# power-supplies.net
KiCad netlist of a schematic drawn in Altium Designer
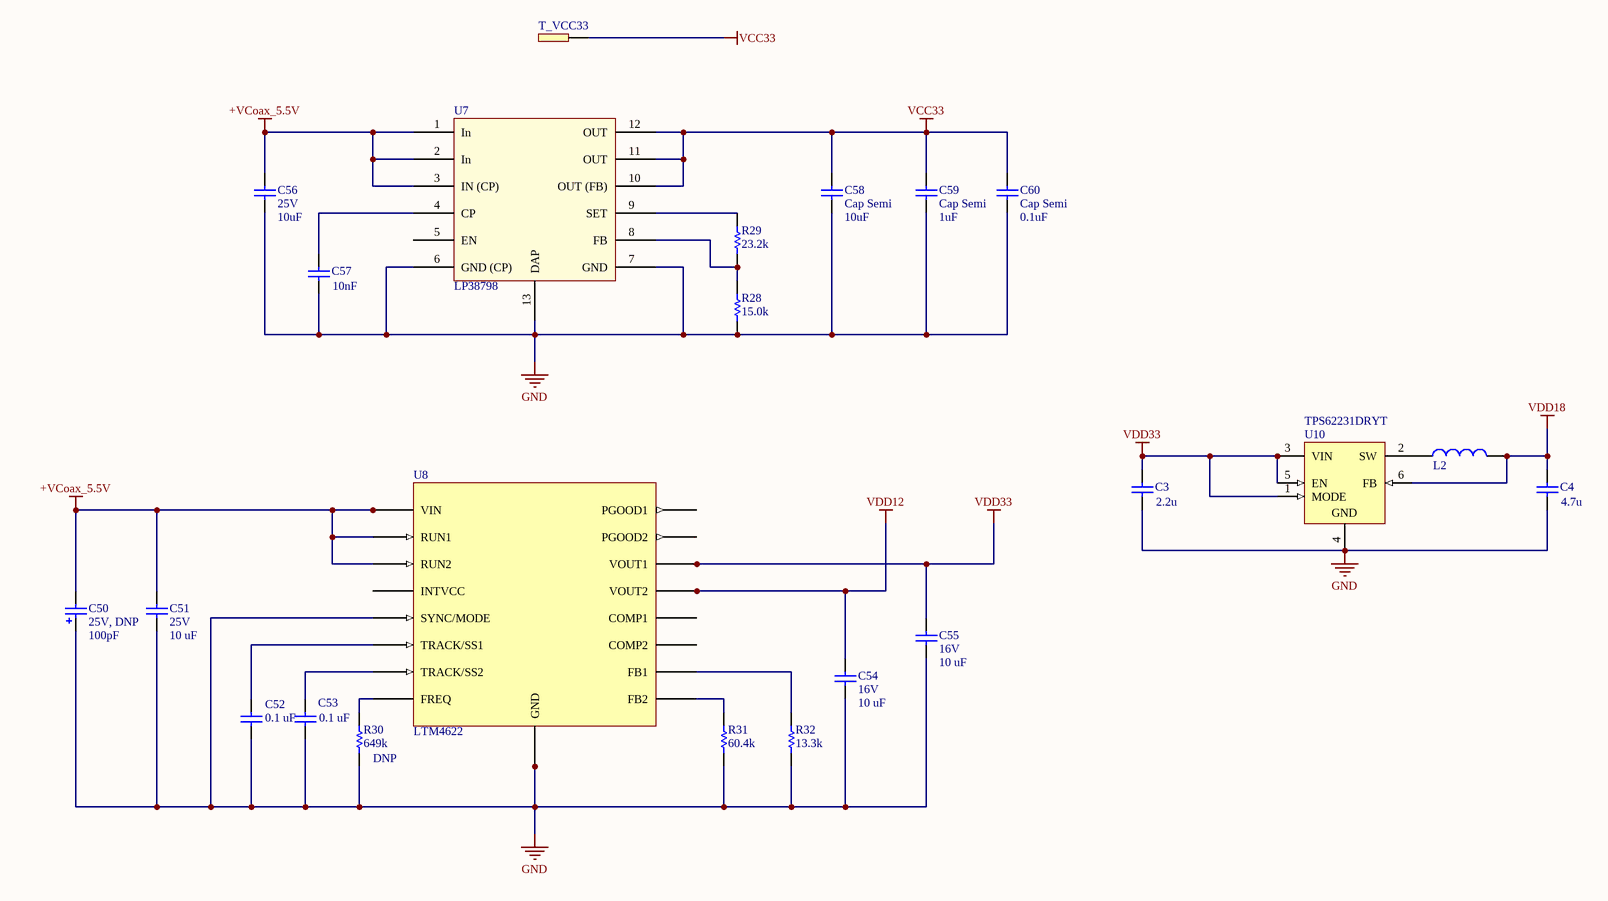
[diagram p0: power-supplies.SchDoc]

(export (version "E")
  (design (tool "Eeschema 10.0.6"))
  (components
    (comp (ref "C3")
      (value "2.2u")
      (footprint "Cap_0402")
      (description "Capacitor")
      (fields (field (name "Comment") "X7R Ceramic") (field (name "PUBLISHER") "Altium Limited"))
      (libsource (lib "Miscellaneous Devices") (part "Cap"))
    )
    (comp (ref "C4")
      (value "4.7u")
      (footprint "Cap_0402")
      (description "Capacitor")
      (fields (field (name "Comment") "X7R Ceramic") (field (name "PUBLISHER") "Altium Limited"))
      (libsource (lib "Miscellaneous Devices") (part "Cap"))
    )
    (comp (ref "C50")
      (value "25V, DNP")
      (footprint "C0805")
      (description "Polarized Capacitor (Surface Mount)")
      (fields (field (name "ALTIUM_VALUE") "100pF") (field (name "PUBLISHER") "Altium Limited"))
      (libsource (lib "Miscellaneous Devices") (part "Cap Pol3"))
    )
    (comp (ref "C51")
      (value "25V")
      (footprint "C1206")
      (description "Capacitor (Semiconductor SIM Model)")
      (fields
        (field (name "ALTIUM_VALUE") "10 uF")
        (field (name "VOLTAGE") "25 V")
        (field (name "PUBLISHER") "Altium Limited")
      )
      (libsource (lib "Miscellaneous Devices") (part "Cap Semi"))
    )
    (comp (ref "C52")
      (value "0.1 uF")
      (footprint "C1206")
      (description "Capacitor (Semiconductor SIM Model)")
      (fields
        (field (name "VOLTAGE") "25 V")
        (field (name "Comment") "25V")
        (field (name "PUBLISHER") "Altium Limited")
      )
      (libsource (lib "Miscellaneous Devices") (part "Cap Semi"))
    )
    (comp (ref "C53")
      (value "0.1 uF")
      (footprint "C1206")
      (description "Capacitor (Semiconductor SIM Model)")
      (fields
        (field (name "VOLTAGE") "25 V")
        (field (name "Comment") "25V")
        (field (name "PUBLISHER") "Altium Limited")
      )
      (libsource (lib "Miscellaneous Devices") (part "Cap Semi"))
    )
    (comp (ref "C54")
      (value "16V")
      (footprint "C1206")
      (description "Capacitor (Semiconductor SIM Model)")
      (fields
        (field (name "ALTIUM_VALUE") "10 uF")
        (field (name "VOLTAGE") "16 V")
        (field (name "PUBLISHER") "Altium Limited")
      )
      (libsource (lib "Miscellaneous Devices") (part "Cap Semi"))
    )
    (comp (ref "C55")
      (value "16V")
      (footprint "C1206")
      (description "Capacitor (Semiconductor SIM Model)")
      (fields
        (field (name "ALTIUM_VALUE") "10 uF")
        (field (name "VOLTAGE") "16 V")
        (field (name "PUBLISHER") "Altium Limited")
      )
      (libsource (lib "Miscellaneous Devices") (part "Cap Semi"))
    )
    (comp (ref "C56")
      (value "25V")
      (footprint "C1206")
      (description "Capacitor (Semiconductor SIM Model)")
      (fields (field (name "ALTIUM_VALUE") "10uF") (field (name "PUBLISHER") "Altium Limited"))
      (libsource (lib "Miscellaneous Devices") (part "Cap Semi"))
    )
    (comp (ref "C57")
      (value "10nF")
      (footprint "0402")
      (description "Capacitor (Semiconductor SIM Model)")
      (fields (field (name "PUBLISHER") "Altium Limited"))
      (libsource (lib "Miscellaneous Devices") (part "Cap Semi"))
    )
    (comp (ref "C58")
      (value "Cap Semi")
      (footprint "Cap-0603")
      (description "Capacitor (Semiconductor SIM Model)")
      (fields (field (name "ALTIUM_VALUE") "10uF") (field (name "PUBLISHER") "Altium Limited"))
      (libsource (lib "Miscellaneous Devices") (part "Cap Semi"))
    )
    (comp (ref "C59")
      (value "Cap Semi")
      (footprint "Cap-0603")
      (description "Capacitor (Semiconductor SIM Model)")
      (fields (field (name "ALTIUM_VALUE") "1uF") (field (name "PUBLISHER") "Altium Limited"))
      (libsource (lib "Miscellaneous Devices") (part "Cap Semi"))
    )
    (comp (ref "C60")
      (value "Cap Semi")
      (footprint "Cap-0603")
      (description "Capacitor (Semiconductor SIM Model)")
      (fields (field (name "ALTIUM_VALUE") "0.1uF") (field (name "PUBLISHER") "Altium Limited"))
      (libsource (lib "Miscellaneous Devices") (part "Cap Semi"))
    )
    (comp (ref "L2")
      (value "Ferrite Bead")
      (footprint "LQM21PN2R2MC0D")
      (libsource (lib "DA_Component_Library") (part "Ferrite Bead"))
    )
    (comp (ref "R28")
      (value "15.0k")
      (footprint "Res_0402")
      (description "Resistor")
      (fields (field (name "Comment") "Res1") (field (name "PUBLISHER") "Altium Limited"))
      (libsource (lib "Miscellaneous Devices") (part "Res1"))
    )
    (comp (ref "R29")
      (value "23.2k")
      (footprint "Res_0402")
      (description "Resistor")
      (fields (field (name "Comment") "Res1") (field (name "PUBLISHER") "Altium Limited"))
      (libsource (lib "Miscellaneous Devices") (part "Res1"))
    )
    (comp (ref "R30")
      (value "DNP")
      (footprint "Res_0402")
      (description "Resistor")
      (fields (field (name "ALTIUM_VALUE") "649k") (field (name "PUBLISHER") "Altium Limited"))
      (libsource (lib "Miscellaneous Devices") (part "Res1"))
    )
    (comp (ref "R31")
      (value "60.4k")
      (footprint "Res_0402")
      (description "Resistor")
      (fields (field (name "Comment") "649k (DNP)") (field (name "PUBLISHER") "Altium Limited"))
      (libsource (lib "Miscellaneous Devices") (part "Res1"))
    )
    (comp (ref "R32")
      (value "13.3k")
      (footprint "Res_0402")
      (description "Resistor")
      (fields (field (name "PUBLISHER") "Altium Limited"))
      (libsource (lib "Miscellaneous Devices") (part "Res1"))
    )
    (comp (ref "T_VCC33")
      (value "Header_1PIN")
      (footprint "JUMPER1PIN")
      (libsource (lib "Jack_SCH_Lib1") (part "Header_1PIN"))
    )
    (comp (ref "U7")
      (value "LP38798")
      (footprint "DFN12")
      (description "Low Noise Positive LDO")
      (libsource (lib "jonnew") (part "Component_1"))
    )
    (comp (ref "U8") (value "LTM4622") (footprint "LGA5x5") (libsource (lib "jonnew") (part "LTM4622")))
    (comp (ref "U10")
      (value "TPS62231DRYT")
      (footprint "TPS62231DRYT")
      (fields (field (name "MANUFACTURER") "Texas Instruments"))
      (libsource (lib "TI Power Management Step-Down Regulator") (part "TPS62231DRYT"))
    )
  )
  (nets
    (net (code "1") (name "+VCoax_5.5V") (class "Default")
      (node (ref "C50") (pin "2") (pinfunction "2_2") (pintype "passive"))
      (node (ref "C51") (pin "2") (pinfunction "2_2") (pintype "passive"))
      (node (ref "C56") (pin "2") (pinfunction "2_2") (pintype "passive"))
      (node (ref "U7") (pin "1") (pinfunction "In_1") (pintype "power_in"))
      (node (ref "U7") (pin "2") (pinfunction "In_2") (pintype "power_in"))
      (node (ref "U7") (pin "3") (pinfunction "IN_(CP)_3") (pintype "power_in"))
      (node (ref "U8") (pin "A2") (pinfunction "VIN_A2") (pintype "power_in"))
      (node (ref "U8") (pin "B2") (pinfunction "RUN2_B2") (pintype "input"))
      (node (ref "U8") (pin "B3") (pinfunction "VIN_B3") (pintype "passive"))
      (node (ref "U8") (pin "D2") (pinfunction "RUN1_D2") (pintype "input"))
      (node (ref "U8") (pin "D3") (pinfunction "VIN_D3") (pintype "passive"))
      (node (ref "U8") (pin "E2") (pinfunction "VIN_E2") (pintype "passive"))
    )
    (net (code "2") (name "GND") (class "Default")
      (node (ref "C3") (pin "1") (pinfunction "1_1") (pintype "passive"))
      (node (ref "C4") (pin "1") (pinfunction "1_1") (pintype "passive"))
      (node (ref "C50") (pin "1") (pinfunction "1_1") (pintype "passive"))
      (node (ref "C51") (pin "1") (pinfunction "1_1") (pintype "passive"))
      (node (ref "C52") (pin "1") (pinfunction "1_1") (pintype "passive"))
      (node (ref "C53") (pin "1") (pinfunction "1_1") (pintype "passive"))
      (node (ref "C54") (pin "1") (pinfunction "1_1") (pintype "passive"))
      (node (ref "C55") (pin "1") (pinfunction "1_1") (pintype "passive"))
      (node (ref "C56") (pin "1") (pinfunction "1_1") (pintype "passive"))
      (node (ref "C57") (pin "1") (pinfunction "1_1") (pintype "passive"))
      (node (ref "C58") (pin "1") (pinfunction "1_1") (pintype "passive"))
      (node (ref "C59") (pin "1") (pinfunction "1_1") (pintype "passive"))
      (node (ref "C60") (pin "1") (pinfunction "1_1") (pintype "passive"))
      (node (ref "R28") (pin "2") (pinfunction "2_2") (pintype "passive"))
      (node (ref "R30") (pin "2") (pinfunction "2_2") (pintype "passive"))
      (node (ref "R31") (pin "2") (pinfunction "2_2") (pintype "passive"))
      (node (ref "R32") (pin "2") (pinfunction "2_2") (pintype "passive"))
      (node (ref "U10") (pin "4") (pinfunction "GND_4") (pintype "power_in"))
      (node (ref "U7") (pin "13") (pinfunction "DAP_13") (pintype "passive"))
      (node (ref "U7") (pin "6") (pinfunction "GND_(CP)_6") (pintype "passive"))
      (node (ref "U7") (pin "7") (pinfunction "GND_7") (pintype "power_in"))
      (node (ref "U8") (pin "B5") (pinfunction "GND_B5") (pintype "passive"))
      (node (ref "U8") (pin "C1") (pinfunction "GND_C1") (pintype "power_in"))
      (node (ref "U8") (pin "C2") (pinfunction "GND_C2") (pintype "passive"))
      (node (ref "U8") (pin "C5") (pinfunction "SYNC/MODE_C5") (pintype "input"))
      (node (ref "U8") (pin "D5") (pinfunction "GND_D5") (pintype "passive"))
    )
    (net (code "3") (name "Net-(U7-CP)") (class "Default")
      (node (ref "C57") (pin "2") (pinfunction "2_2") (pintype "passive"))
      (node (ref "U7") (pin "4") (pinfunction "CP_4") (pintype "passive"))
    )
    (net (code "4") (name "Net-(U7-FB)") (class "Default")
      (node (ref "R28") (pin "1") (pinfunction "1_1") (pintype "passive"))
      (node (ref "R29") (pin "2") (pinfunction "2_2") (pintype "passive"))
      (node (ref "U7") (pin "8") (pinfunction "FB_8") (pintype "passive"))
    )
    (net (code "5") (name "Net-(U7-SET)") (class "Default")
      (node (ref "R29") (pin "1") (pinfunction "1_1") (pintype "passive"))
      (node (ref "U7") (pin "9") (pinfunction "SET_9") (pintype "passive"))
    )
    (net (code "6") (name "Net-(U8-FB1)") (class "Default")
      (node (ref "R32") (pin "1") (pinfunction "1_1") (pintype "passive"))
      (node (ref "U8") (pin "E4") (pinfunction "FB1_E4") (pintype "passive"))
    )
    (net (code "7") (name "Net-(U8-FB2)") (class "Default")
      (node (ref "R31") (pin "1") (pinfunction "1_1") (pintype "passive"))
      (node (ref "U8") (pin "A4") (pinfunction "FB2_A4") (pintype "passive"))
    )
    (net (code "8") (name "Net-(U8-FREQ)") (class "Default")
      (node (ref "R30") (pin "1") (pinfunction "1_1") (pintype "passive"))
      (node (ref "U8") (pin "C4") (pinfunction "FREQ_C4") (pintype "passive"))
    )
    (net (code "9") (name "Net-(U8-TRACK{slash}SS1)") (class "Default")
      (node (ref "C52") (pin "2") (pinfunction "2_2") (pintype "passive"))
      (node (ref "U8") (pin "E5") (pinfunction "TRACK/SS1_E5") (pintype "input"))
    )
    (net (code "10") (name "Net-(U8-TRACK{slash}SS2)") (class "Default")
      (node (ref "C53") (pin "2") (pinfunction "2_2") (pintype "passive"))
      (node (ref "U8") (pin "A3") (pinfunction "TRACK/SS2_A3") (pintype "input"))
    )
    (net (code "11") (name "Net-(U10-SW)") (class "Default")
      (node (ref "L2") (pin "1") (pinfunction "1_1") (pintype "passive"))
      (node (ref "U10") (pin "2") (pinfunction "SW_2") (pintype "power_in"))
    )
    (net (code "12") (name "VCC33") (class "Default")
      (node (ref "C58") (pin "2") (pinfunction "2_2") (pintype "passive"))
      (node (ref "C59") (pin "2") (pinfunction "2_2") (pintype "passive"))
      (node (ref "C60") (pin "2") (pinfunction "2_2") (pintype "passive"))
      (node (ref "T_VCC33") (pin "0") (pinfunction "0_0") (pintype "passive"))
      (node (ref "U7") (pin "10") (pinfunction "OUT_(FB)_10") (pintype "passive"))
      (node (ref "U7") (pin "11") (pinfunction "OUT_11") (pintype "power_in"))
      (node (ref "U7") (pin "12") (pinfunction "OUT_12") (pintype "power_in"))
    )
    (net (code "13") (name "VDD12") (class "Default")
      (node (ref "C54") (pin "2") (pinfunction "2_2") (pintype "passive"))
      (node (ref "U8") (pin "A1") (pinfunction "VOUT2_A1") (pintype "power_in"))
      (node (ref "U8") (pin "B1") (pinfunction "VOUT2_B1") (pintype "passive"))
    )
    (net (code "14") (name "VDD18") (class "Default")
      (node (ref "C4") (pin "2") (pinfunction "2_2") (pintype "passive"))
      (node (ref "L2") (pin "2") (pinfunction "2_2") (pintype "passive"))
      (node (ref "U10") (pin "6") (pinfunction "FB_6") (pintype "input"))
    )
    (net (code "15") (name "VDD33") (class "Default")
      (node (ref "C3") (pin "2") (pinfunction "2_2") (pintype "passive"))
      (node (ref "C55") (pin "2") (pinfunction "2_2") (pintype "passive"))
      (node (ref "U10") (pin "1") (pinfunction "MODE_1") (pintype "input"))
      (node (ref "U10") (pin "3") (pinfunction "VIN_3") (pintype "power_in"))
      (node (ref "U10") (pin "5") (pinfunction "EN_5") (pintype "input"))
      (node (ref "U8") (pin "D1") (pinfunction "VOUT1_D1") (pintype "power_in"))
      (node (ref "U8") (pin "E1") (pinfunction "VOUT1_E1") (pintype "passive"))
    )
    (net (code "16") (name "unconnected-(U7-EN-Pad5)") (class "Default")
      (node (ref "U7") (pin "5") (pinfunction "EN_5") (pintype "passive"))
    )
    (net (code "17") (name "unconnected-(U8-COMP1-PadE5)") (class "Default")
      (node (ref "U8") (pin "E5") (pinfunction "COMP1_E5") (pintype "passive"))
    )
    (net (code "18") (name "unconnected-(U8-COMP2-PadA5)") (class "Default")
      (node (ref "U8") (pin "A5") (pinfunction "COMP2_A5") (pintype "passive"))
    )
    (net (code "19") (name "unconnected-(U8-INTVCC-PadC3)") (class "Default")
      (node (ref "U8") (pin "C3") (pinfunction "INTVCC_C3") (pintype "passive"))
    )
    (net (code "20") (name "unconnected-(U8-PGOOD1-PadD4)") (class "Default")
      (node (ref "U8") (pin "D4") (pinfunction "PGOOD1_D4") (pintype "output"))
    )
    (net (code "21") (name "unconnected-(U8-PGOOD2-PadB4)") (class "Default")
      (node (ref "U8") (pin "B4") (pinfunction "PGOOD2_B4") (pintype "output"))
    )
  )
)
